# Relay_Board.net
KiCad netlist of a schematic drawn in Altium Designer
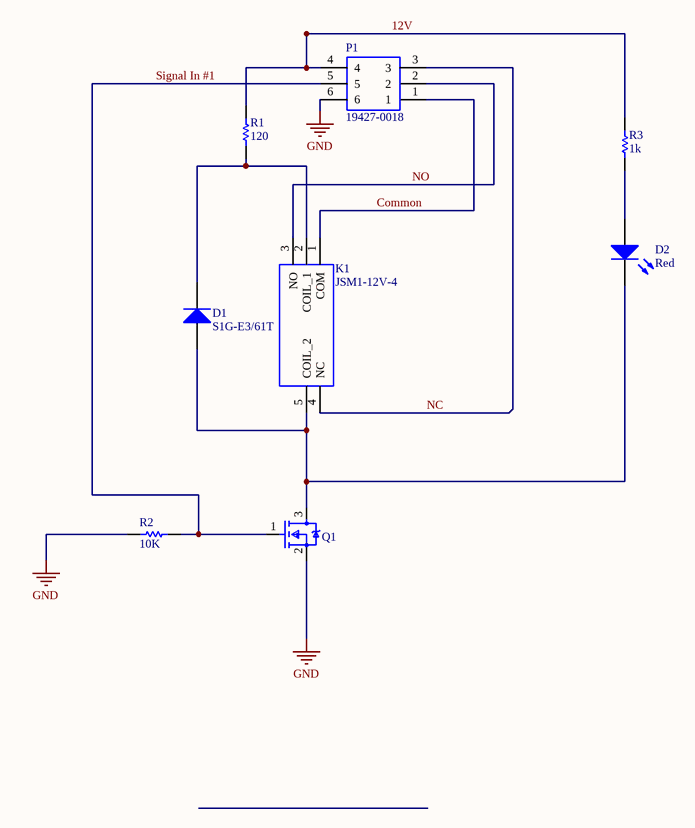
[diagram p0: Relay Board.SchDoc]

(export (version "E")
  (design (tool "Eeschema 10.0.6"))
  (components
    (comp (ref "D1")
      (value "S1G-E3/61T")
      (footprint "VISH-DO-214AC-SMA-2_N")
      (fields (field (name "MANUFACTURER") "Vishay Semiconductor"))
      (libsource (lib "Integrated_Library1") (part "S1G-E3/61T"))
    )
    (comp (ref "D2")
      (value "Red")
      (footprint "LEDC3216X120NRED")
      (description "Typical RED, GREEN, YELLOW, AMBER GaAs LED")
      (fields
        (field (name "MANUFACTURER") "Broadcom Avago")
        (field (name "MANUFACTURER PART NUMBER") "HSMY-C150")
        (field (name "PUBLISHER") "Altium Limited")
      )
      (libsource (lib "Candunio v2018_7_27") (part "LED2_2"))
    )
    (comp (ref "K1")
      (value "JSM1-12V-4")
      (footprint "JSM112V4")
      (description "PANASONIC ELECTRIC WORKS - JSM1-12V-4 - RELAY, AUTOMOTIVE, SPDT, 16VDC, 10A")
      (libsource (lib "Integrated_Library1") (part "JSM1-12V-4"))
    )
    (comp (ref "P1")
      (value "19427-0018")
      (footprint "MX150L 6pin")
      (description "MX150L 6pin")
      (libsource (lib "Molex MX150L") (part "19427-0018 MX150L 6pin"))
    )
    (comp (ref "Q1")
      (value "Trans_Diodes_2N7002-7-F_eec")
      (footprint "Diodes_2N7002-7-F_0")
      (description "TRANS MOSFET N-CH 60V 115MA SOT23-3")
      (fields (field (name "PART NUMBER") "2N7002-7-F") (field (name "MANUFACTURER") "Diodes"))
      (libsource (lib "Integrated_Library1") (part "Trans_Diodes_2N7002-7-F_eec"))
    )
    (comp (ref "R1")
      (value "120")
      (footprint "RESC3216X60N")
      (description "Resistor")
      (fields
        (field (name "MANUFACTURER") "Stackpole Electronics")
        (field (name "MANUFACTURER PART NUMBER") "RNCP1206FTD1K00")
      )
      (libsource (lib "Candunio v2018_8_8") (part "Res1"))
    )
    (comp (ref "R2")
      (value "10K")
      (footprint "RESC3216X60N")
      (description "Resistor")
      (fields
        (field (name "MANUFACTURER") "Stackpole Electronics")
        (field (name "MANUFACTURER PART NUMBER") "RNCP1206FTD1K00")
      )
      (libsource (lib "Candunio v2018_8_8") (part "Res1"))
    )
    (comp (ref "R3")
      (value "1k")
      (footprint "RESC3216X60N")
      (description "Resistor")
      (fields
        (field (name "MANUFACTURER") "Stackpole Electronics")
        (field (name "MANUFACTURER PART NUMBER") "RNCP1206FTD1K00")
      )
      (libsource (lib "Candunio v2018_7_27") (part "Res1"))
    )
  )
  (nets
    (net (code "1") (name "/12V") (class "Default")
      (node (ref "P1") (pin "4") (pinfunction "4_4") (pintype "passive"))
      (node (ref "R1") (pin "2") (pinfunction "2_2") (pintype "passive"))
      (node (ref "R3") (pin "2") (pinfunction "2_2") (pintype "passive"))
    )
    (net (code "2") (name "/Common") (class "Default")
      (node (ref "K1") (pin "1") (pinfunction "COM_1") (pintype "passive"))
      (node (ref "P1") (pin "1") (pinfunction "1_1") (pintype "passive"))
    )
    (net (code "3") (name "/NC") (class "Default")
      (node (ref "K1") (pin "4") (pinfunction "NC_4") (pintype "passive"))
      (node (ref "P1") (pin "3") (pinfunction "3_3") (pintype "passive"))
    )
    (net (code "4") (name "/NO") (class "Default")
      (node (ref "K1") (pin "3") (pinfunction "NO_3") (pintype "passive"))
      (node (ref "P1") (pin "2") (pinfunction "2_2") (pintype "passive"))
    )
    (net (code "6") (name "/Signal In #1") (class "Default")
      (node (ref "P1") (pin "5") (pinfunction "5_5") (pintype "passive"))
      (node (ref "Q1") (pin "1") (pinfunction "Gate_1") (pintype "passive"))
      (node (ref "R2") (pin "1") (pinfunction "1_1") (pintype "passive"))
    )
    (net (code "7") (name "GND") (class "Default")
      (node (ref "P1") (pin "6") (pinfunction "6_6") (pintype "passive"))
      (node (ref "Q1") (pin "2") (pinfunction "Source_2") (pintype "passive"))
      (node (ref "R2") (pin "2") (pinfunction "2_2") (pintype "passive"))
    )
    (net (code "8") (name "Net-(D1-A)") (class "Default")
      (node (ref "D1") (pin "1") (pinfunction "A_1") (pintype "passive"))
      (node (ref "D2") (pin "2") (pinfunction "K_2") (pintype "passive"))
      (node (ref "K1") (pin "5") (pinfunction "COIL_2_5") (pintype "passive"))
      (node (ref "Q1") (pin "3") (pinfunction "Drain_3") (pintype "passive"))
    )
    (net (code "9") (name "Net-(D1-K)") (class "Default")
      (node (ref "D1") (pin "2") (pinfunction "K_2") (pintype "passive"))
      (node (ref "K1") (pin "2") (pinfunction "COIL_1_2") (pintype "passive"))
      (node (ref "R1") (pin "1") (pinfunction "1_1") (pintype "passive"))
    )
    (net (code "10") (name "Net-(D2-A)") (class "Default")
      (node (ref "D2") (pin "1") (pinfunction "A_1") (pintype "passive"))
      (node (ref "R3") (pin "1") (pinfunction "1_1") (pintype "passive"))
    )
  )
)
